# MintyCharger_9V_Rev_A.net
KiCad netlist of a schematic drawn in EAGLE
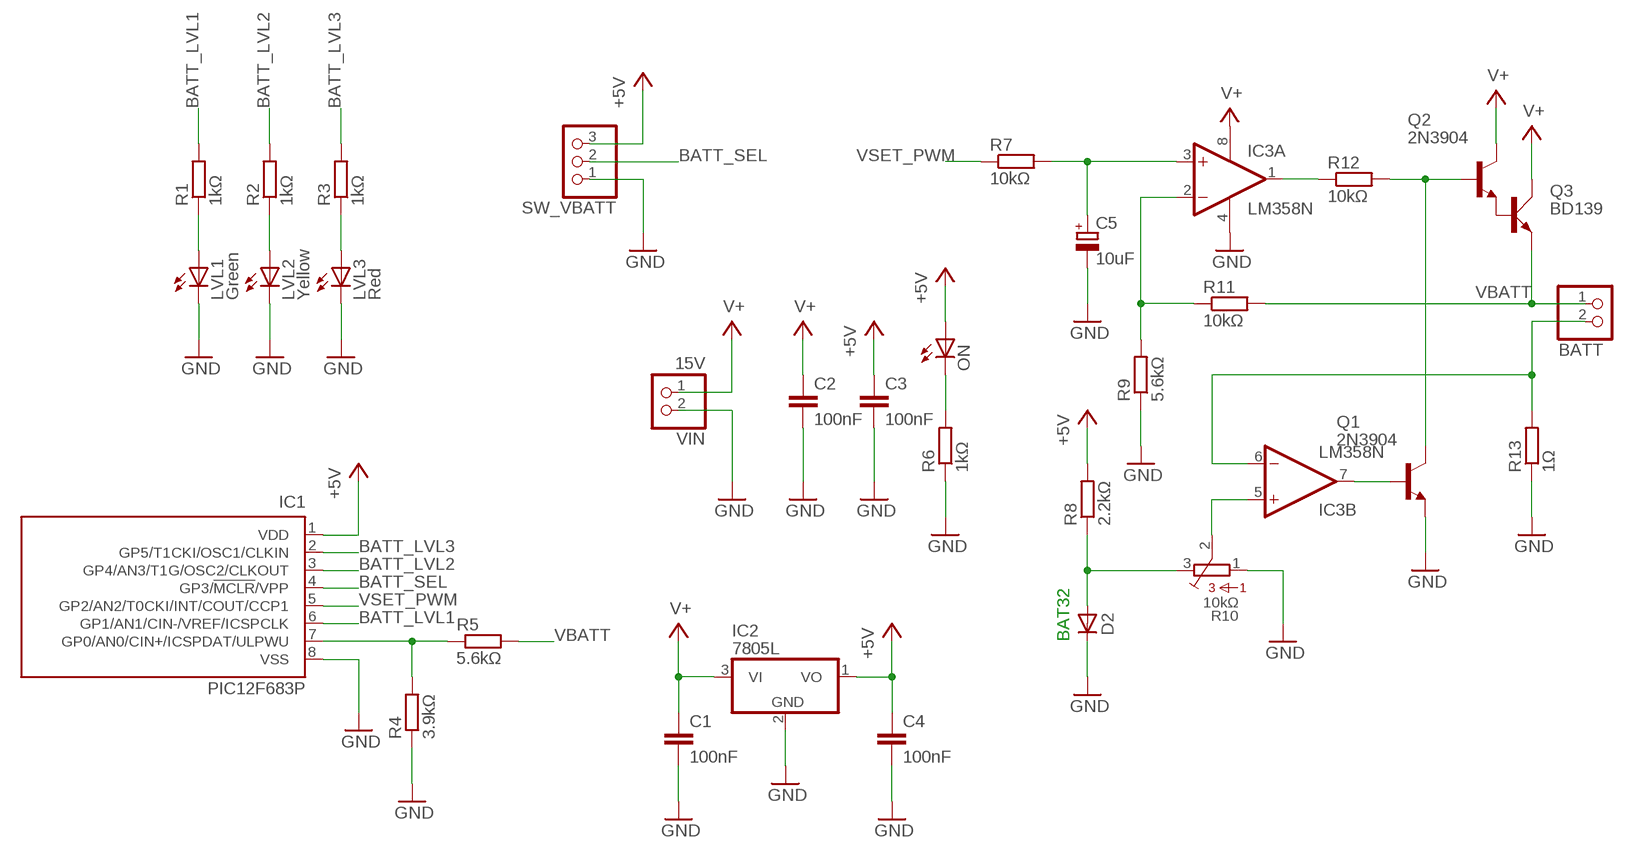
[diagram p0: schematic, sheet 1]

(export (version "E")
  (design (tool "Eeschema 10.0.6"))
  (components
    (comp (ref "BATT")
      (value "JST_2PIN-THM")
      (footprint "eagle-import:JST-PH-2-THM")
      (libsource (lib "eagle-import") (part "JST_2PIN-THM"))
    )
    (comp (ref "C1")
      (value "100nF")
      (footprint "eagle-import:C025-025X050")
      (libsource (lib "eagle-import") (part "C-EU025-025X050"))
    )
    (comp (ref "C2")
      (value "100nF")
      (footprint "eagle-import:C025-025X050")
      (libsource (lib "eagle-import") (part "C-EU025-025X050"))
    )
    (comp (ref "C3")
      (value "100nF")
      (footprint "eagle-import:C025-025X050")
      (libsource (lib "eagle-import") (part "C-EU025-025X050"))
    )
    (comp (ref "C4")
      (value "100nF")
      (footprint "eagle-import:C025-025X050")
      (libsource (lib "eagle-import") (part "C-EU025-025X050"))
    )
    (comp (ref "C5")
      (value "10uF")
      (footprint "eagle-import:E2,5-6")
      (libsource (lib "eagle-import") (part "CPOL-EUE2.5-6"))
    )
    (comp (ref "D2")
      (value "1N4148DO35-7")
      (footprint "eagle-import:DO35-7")
      (libsource (lib "eagle-import") (part "1N4148DO35-7"))
    )
    (comp (ref "IC1")
      (value "PIC12F683P")
      (footprint "eagle-import:DIL8")
      (fields (field (name "MF") "MICROCHIP") (field (name "MPN") "PIC12F683-I/P"))
      (libsource (lib "eagle-import") (part "PIC12F683P"))
    )
    (comp (ref "IC2")
      (value "7805L")
      (footprint "eagle-import:TO92")
      (libsource (lib "eagle-import") (part "78L05"))
    )
    (comp (ref "IC3")
      (value "LM358N")
      (footprint "eagle-import:DIL08")
      (libsource (lib "eagle-import") (part "LM358N"))
    )
    (comp (ref "LVL1")
      (value "Green")
      (footprint "eagle-import:LED2X5")
      (libsource (lib "eagle-import") (part "LEDSQR2X5"))
    )
    (comp (ref "LVL2")
      (value "Yellow")
      (footprint "eagle-import:LED2X5")
      (libsource (lib "eagle-import") (part "LEDSQR2X5"))
    )
    (comp (ref "LVL3")
      (value "Red")
      (footprint "eagle-import:LED2X5")
      (libsource (lib "eagle-import") (part "LEDSQR2X5"))
    )
    (comp (ref "ON")
      (value "LEDSQR2X5")
      (footprint "eagle-import:LED2X5")
      (libsource (lib "eagle-import") (part "LEDSQR2X5"))
    )
    (comp (ref "Q1")
      (value "2N3904")
      (footprint "eagle-import:TO92")
      (libsource (lib "eagle-import") (part "2N3904"))
    )
    (comp (ref "Q2")
      (value "2N3904")
      (footprint "eagle-import:TO92")
      (libsource (lib "eagle-import") (part "2N3904"))
    )
    (comp (ref "Q3")
      (value "BD139")
      (footprint "eagle-import:TO126AV")
      (libsource (lib "eagle-import") (part "BD139"))
    )
    (comp (ref "R1")
      (value "1kΩ")
      (footprint "eagle-import:0207_10")
      (libsource (lib "eagle-import") (part "R-EU_0207/10"))
    )
    (comp (ref "R2")
      (value "1kΩ")
      (footprint "eagle-import:0207_10")
      (libsource (lib "eagle-import") (part "R-EU_0207/10"))
    )
    (comp (ref "R3")
      (value "1kΩ")
      (footprint "eagle-import:0207_10")
      (libsource (lib "eagle-import") (part "R-EU_0207/10"))
    )
    (comp (ref "R4")
      (value "3.9kΩ")
      (footprint "eagle-import:0207_10")
      (libsource (lib "eagle-import") (part "R-EU_0207/10"))
    )
    (comp (ref "R5")
      (value "5.6kΩ")
      (footprint "eagle-import:0207_10")
      (libsource (lib "eagle-import") (part "resistor_R-EU_0207/10"))
    )
    (comp (ref "R6")
      (value "1kΩ")
      (footprint "eagle-import:0207_10")
      (libsource (lib "eagle-import") (part "R-EU_0207/10"))
    )
    (comp (ref "R7")
      (value "10kΩ")
      (footprint "eagle-import:0207_10")
      (libsource (lib "eagle-import") (part "resistor_R-EU_0207/10"))
    )
    (comp (ref "R8")
      (value "2.2kΩ")
      (footprint "eagle-import:0207_10")
      (libsource (lib "eagle-import") (part "R-EU_0207/10"))
    )
    (comp (ref "R9")
      (value "5.6kΩ")
      (footprint "eagle-import:0207_10")
      (libsource (lib "eagle-import") (part "R-EU_0207/10"))
    )
    (comp (ref "R10")
      (value "10kΩ")
      (footprint "eagle-import:3362U")
      (libsource (lib "eagle-import") (part "3362U"))
    )
    (comp (ref "R11")
      (value "10kΩ")
      (footprint "eagle-import:0207_10")
      (libsource (lib "eagle-import") (part "R-EU_0207/10"))
    )
    (comp (ref "R12")
      (value "10kΩ")
      (footprint "eagle-import:0207_10")
      (libsource (lib "eagle-import") (part "R-EU_0207/10"))
    )
    (comp (ref "R13")
      (value "1Ω")
      (footprint "eagle-import:0207_10")
      (libsource (lib "eagle-import") (part "R-EU_0207/10"))
    )
    (comp (ref "SW_VBATT")
      (value "PINHD-1X3")
      (footprint "eagle-import:1X03")
      (libsource (lib "eagle-import") (part "PINHD-1X3"))
    )
    (comp (ref "VIN")
      (value "15V")
      (footprint "eagle-import:JST-PH-2-THM")
      (libsource (lib "eagle-import") (part "JST_2PIN-THM"))
    )
  )
  (nets
    (net (code "1") (name "+5V") (class "Default")
      (node (ref "C3") (pin "1") (pinfunction "1_1") (pintype "passive"))
      (node (ref "C4") (pin "1") (pinfunction "1_1") (pintype "passive"))
      (node (ref "IC1") (pin "1") (pinfunction "VDD_1") (pintype "power_in"))
      (node (ref "IC2") (pin "1") (pinfunction "VO_1") (pintype "passive"))
      (node (ref "ON") (pin "A") (pinfunction "A_A") (pintype "passive"))
      (node (ref "R8") (pin "2") (pinfunction "2_2") (pintype "passive"))
      (node (ref "SW_VBATT") (pin "3") (pinfunction "3_3") (pintype "passive"))
    )
    (net (code "2") (name "/BATT_LVL1") (class "Default")
      (node (ref "IC1") (pin "6") (pinfunction "GP1/AN1/CIN-/VREF/ICSPCLK_6") (pintype "bidirectional"))
      (node (ref "R1") (pin "2") (pinfunction "2_2") (pintype "passive"))
    )
    (net (code "3") (name "/BATT_LVL2") (class "Default")
      (node (ref "IC1") (pin "3") (pinfunction "GP4/AN3/T1G/OSC2/CLKOUT_3") (pintype "bidirectional"))
      (node (ref "R2") (pin "2") (pinfunction "2_2") (pintype "passive"))
    )
    (net (code "4") (name "/BATT_LVL3") (class "Default")
      (node (ref "IC1") (pin "2") (pinfunction "GP5/T1CKI/OSC1/CLKIN_2") (pintype "bidirectional"))
      (node (ref "R3") (pin "2") (pinfunction "2_2") (pintype "passive"))
    )
    (net (code "5") (name "/BATT_SEL") (class "Default")
      (node (ref "IC1") (pin "4") (pinfunction "GP3/~{MCLR}/VPP_4") (pintype "bidirectional"))
      (node (ref "SW_VBATT") (pin "2") (pinfunction "2_2") (pintype "passive"))
    )
    (net (code "6") (name "/VBATT") (class "Default")
      (node (ref "BATT") (pin "1") (pinfunction "2_1") (pintype "passive"))
      (node (ref "Q3") (pin "E") (pinfunction "E_E") (pintype "passive"))
      (node (ref "R11") (pin "2") (pinfunction "2_2") (pintype "passive"))
      (node (ref "R5") (pin "2") (pinfunction "2_2") (pintype "passive"))
    )
    (net (code "7") (name "/VSET_PWM") (class "Default")
      (node (ref "IC1") (pin "5") (pinfunction "GP2/AN2/T0CKI/INT/COUT/CCP1_5") (pintype "bidirectional"))
      (node (ref "R7") (pin "1") (pinfunction "1_1") (pintype "passive"))
    )
    (net (code "8") (name "GND") (class "Default")
      (node (ref "C1") (pin "2") (pinfunction "2_2") (pintype "passive"))
      (node (ref "C2") (pin "2") (pinfunction "2_2") (pintype "passive"))
      (node (ref "C3") (pin "2") (pinfunction "2_2") (pintype "passive"))
      (node (ref "C4") (pin "2") (pinfunction "2_2") (pintype "passive"))
      (node (ref "C5") (pin "-") (pinfunction "-_-") (pintype "passive"))
      (node (ref "D2") (pin "C") (pinfunction "C_C") (pintype "passive"))
      (node (ref "IC1") (pin "8") (pinfunction "VSS_8") (pintype "power_in"))
      (node (ref "IC2") (pin "2") (pinfunction "GND_2") (pintype "passive"))
      (node (ref "IC3") (pin "4") (pinfunction "V-_4") (pintype "power_in"))
      (node (ref "LVL1") (pin "K") (pinfunction "C_K") (pintype "passive"))
      (node (ref "LVL2") (pin "K") (pinfunction "C_K") (pintype "passive"))
      (node (ref "LVL3") (pin "K") (pinfunction "C_K") (pintype "passive"))
      (node (ref "Q1") (pin "3") (pinfunction "E_3") (pintype "passive"))
      (node (ref "R10") (pin "1") (pinfunction "1_1") (pintype "passive"))
      (node (ref "R13") (pin "1") (pinfunction "1_1") (pintype "passive"))
      (node (ref "R4") (pin "1") (pinfunction "1_1") (pintype "passive"))
      (node (ref "R6") (pin "1") (pinfunction "1_1") (pintype "passive"))
      (node (ref "R9") (pin "1") (pinfunction "1_1") (pintype "passive"))
      (node (ref "SW_VBATT") (pin "1") (pinfunction "1_1") (pintype "passive"))
      (node (ref "VIN") (pin "2") (pinfunction "1_2") (pintype "passive"))
    )
    (net (code "9") (name "Net-(BATT-1)") (class "Default")
      (node (ref "BATT") (pin "2") (pinfunction "1_2") (pintype "passive"))
      (node (ref "IC3") (pin "6") (pinfunction "-IN_6") (pintype "input"))
      (node (ref "R13") (pin "2") (pinfunction "2_2") (pintype "passive"))
    )
    (net (code "10") (name "Net-(D2-PadA)") (class "Default")
      (node (ref "D2") (pin "A") (pinfunction "A_A") (pintype "passive"))
      (node (ref "R10") (pin "3") (pinfunction "3_3") (pintype "passive"))
      (node (ref "R8") (pin "1") (pinfunction "1_1") (pintype "passive"))
    )
    (net (code "11") (name "Net-(IC1-GP0{slash}AN0{slash}CIN+{slash}ICSPDAT{slash}ULPWU)") (class "Default")
      (node (ref "IC1") (pin "7") (pinfunction "GP0/AN0/CIN+/ICSPDAT/ULPWU_7") (pintype "bidirectional"))
      (node (ref "R4") (pin "2") (pinfunction "2_2") (pintype "passive"))
      (node (ref "R5") (pin "1") (pinfunction "1_1") (pintype "passive"))
    )
    (net (code "12") (name "Net-(IC3A-+IN)") (class "Default")
      (node (ref "C5") (pin "+") (pinfunction "+_+") (pintype "passive"))
      (node (ref "IC3") (pin "3") (pinfunction "+IN_3") (pintype "input"))
      (node (ref "R7") (pin "2") (pinfunction "2_2") (pintype "passive"))
    )
    (net (code "13") (name "Net-(IC3A--IN)") (class "Default")
      (node (ref "IC3") (pin "2") (pinfunction "-IN_2") (pintype "input"))
      (node (ref "R11") (pin "1") (pinfunction "1_1") (pintype "passive"))
      (node (ref "R9") (pin "2") (pinfunction "2_2") (pintype "passive"))
    )
    (net (code "14") (name "Net-(IC3A-OUT)") (class "Default")
      (node (ref "IC3") (pin "1") (pinfunction "OUT_1") (pintype "output"))
      (node (ref "R12") (pin "1") (pinfunction "1_1") (pintype "passive"))
    )
    (net (code "15") (name "Net-(IC3B-+IN)") (class "Default")
      (node (ref "IC3") (pin "5") (pinfunction "+IN_5") (pintype "input"))
      (node (ref "R10") (pin "2") (pinfunction "2_2") (pintype "passive"))
    )
    (net (code "16") (name "Net-(IC3B-OUT)") (class "Default")
      (node (ref "IC3") (pin "7") (pinfunction "OUT_7") (pintype "output"))
      (node (ref "Q1") (pin "2") (pinfunction "B_2") (pintype "passive"))
    )
    (net (code "17") (name "Net-(LVL1-PadA)") (class "Default")
      (node (ref "LVL1") (pin "A") (pinfunction "A_A") (pintype "passive"))
      (node (ref "R1") (pin "1") (pinfunction "1_1") (pintype "passive"))
    )
    (net (code "18") (name "Net-(LVL2-PadA)") (class "Default")
      (node (ref "LVL2") (pin "A") (pinfunction "A_A") (pintype "passive"))
      (node (ref "R2") (pin "1") (pinfunction "1_1") (pintype "passive"))
    )
    (net (code "19") (name "Net-(LVL3-PadA)") (class "Default")
      (node (ref "LVL3") (pin "A") (pinfunction "A_A") (pintype "passive"))
      (node (ref "R3") (pin "1") (pinfunction "1_1") (pintype "passive"))
    )
    (net (code "20") (name "Net-(ON-C)") (class "Default")
      (node (ref "ON") (pin "K") (pinfunction "C_K") (pintype "passive"))
      (node (ref "R6") (pin "2") (pinfunction "2_2") (pintype "passive"))
    )
    (net (code "21") (name "Net-(Q1-C)") (class "Default")
      (node (ref "Q1") (pin "1") (pinfunction "C_1") (pintype "passive"))
      (node (ref "Q2") (pin "2") (pinfunction "B_2") (pintype "passive"))
      (node (ref "R12") (pin "2") (pinfunction "2_2") (pintype "passive"))
    )
    (net (code "22") (name "Net-(Q2-E)") (class "Default")
      (node (ref "Q2") (pin "3") (pinfunction "E_3") (pintype "passive"))
      (node (ref "Q3") (pin "B") (pinfunction "B_B") (pintype "passive"))
    )
    (net (code "23") (name "V+") (class "Default")
      (node (ref "C1") (pin "1") (pinfunction "1_1") (pintype "passive"))
      (node (ref "C2") (pin "1") (pinfunction "1_1") (pintype "passive"))
      (node (ref "IC2") (pin "3") (pinfunction "VI_3") (pintype "input"))
      (node (ref "IC3") (pin "8") (pinfunction "V+_8") (pintype "power_in"))
      (node (ref "Q2") (pin "1") (pinfunction "C_1") (pintype "passive"))
      (node (ref "Q3") (pin "C") (pinfunction "C_C") (pintype "passive"))
      (node (ref "VIN") (pin "1") (pinfunction "2_1") (pintype "passive"))
    )
  )
)
